# M152B.net
KiCad netlist of a schematic drawn in EAGLE
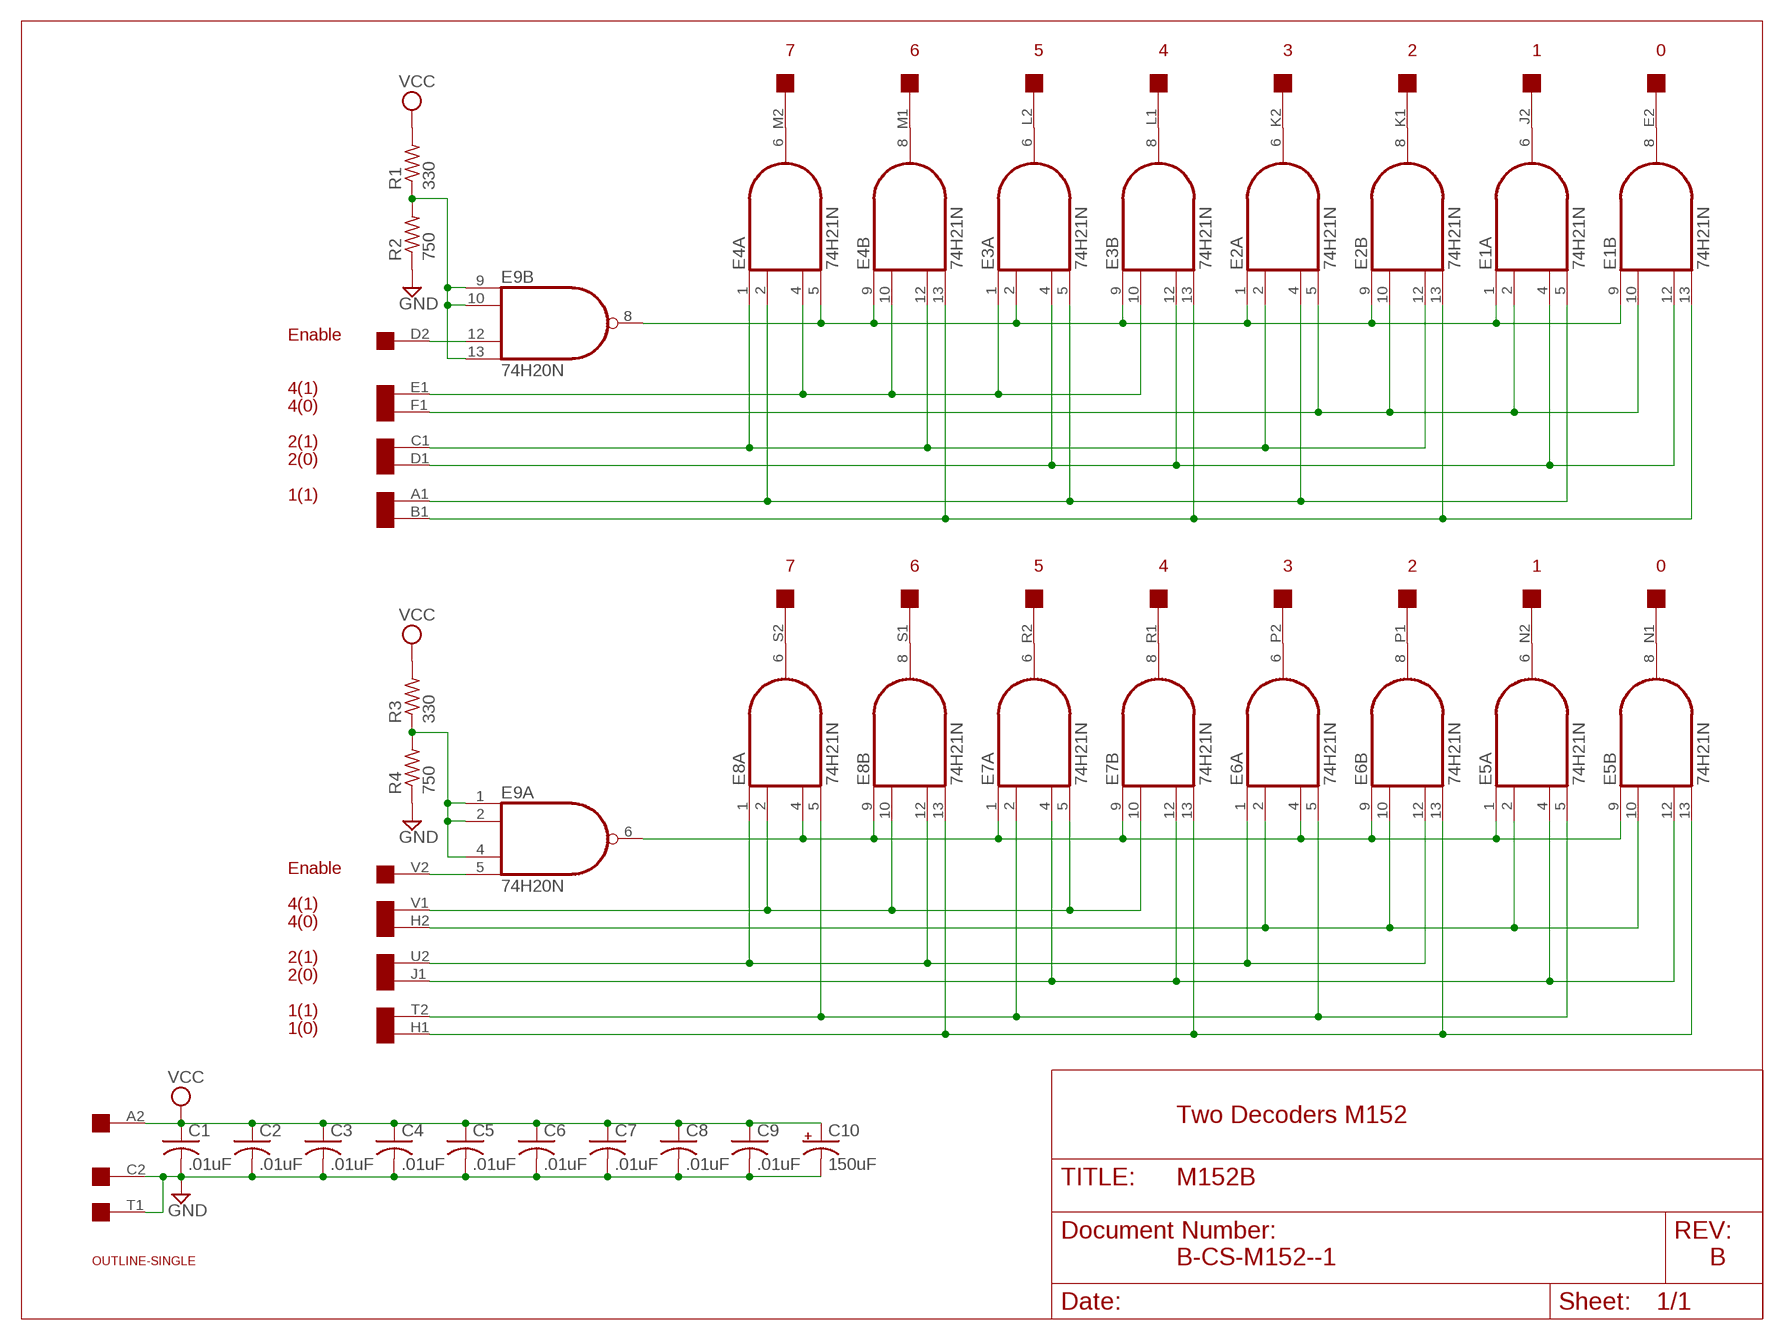
[diagram p0: schematic, sheet 1]

(export (version "E")
  (design (tool "Eeschema 10.0.6"))
  (components
    (comp (ref "C1")
      (value ".01uF")
      (footprint "eagle-import:C050-025X075")
      (libsource (lib "eagle-import") (part "C-US050-025X075"))
    )
    (comp (ref "C2")
      (value ".01uF")
      (footprint "eagle-import:C050-025X075")
      (libsource (lib "eagle-import") (part "C-US050-025X075"))
    )
    (comp (ref "C3")
      (value ".01uF")
      (footprint "eagle-import:C050-025X075")
      (libsource (lib "eagle-import") (part "C-US050-025X075"))
    )
    (comp (ref "C4")
      (value ".01uF")
      (footprint "eagle-import:C050-025X075")
      (libsource (lib "eagle-import") (part "C-US050-025X075"))
    )
    (comp (ref "C5")
      (value ".01uF")
      (footprint "eagle-import:C050-025X075")
      (libsource (lib "eagle-import") (part "C-US050-025X075"))
    )
    (comp (ref "C6")
      (value ".01uF")
      (footprint "eagle-import:C050-025X075")
      (libsource (lib "eagle-import") (part "C-US050-025X075"))
    )
    (comp (ref "C7")
      (value ".01uF")
      (footprint "eagle-import:C050-025X075")
      (libsource (lib "eagle-import") (part "C-US050-025X075"))
    )
    (comp (ref "C8")
      (value ".01uF")
      (footprint "eagle-import:C050-025X075")
      (libsource (lib "eagle-import") (part "C-US050-025X075"))
    )
    (comp (ref "C9")
      (value ".01uF")
      (footprint "eagle-import:C050-025X075")
      (libsource (lib "eagle-import") (part "C-US050-025X075"))
    )
    (comp (ref "C10")
      (value "150uF")
      (footprint "eagle-import:E25-9")
      (libsource (lib "eagle-import") (part "CPOL-USE25-9AXIAL"))
    )
    (comp (ref "E1")
      (value "74H21N")
      (footprint "eagle-import:DIL14")
      (libsource (lib "eagle-import") (part "7421NLS"))
    )
    (comp (ref "E2")
      (value "74H21N")
      (footprint "eagle-import:DIL14")
      (libsource (lib "eagle-import") (part "7421NLS"))
    )
    (comp (ref "E3")
      (value "74H21N")
      (footprint "eagle-import:DIL14")
      (libsource (lib "eagle-import") (part "7421NLS"))
    )
    (comp (ref "E4")
      (value "74H21N")
      (footprint "eagle-import:DIL14")
      (libsource (lib "eagle-import") (part "7421NLS"))
    )
    (comp (ref "E5")
      (value "74H21N")
      (footprint "eagle-import:DIL14")
      (libsource (lib "eagle-import") (part "7421NLS"))
    )
    (comp (ref "E6")
      (value "74H21N")
      (footprint "eagle-import:DIL14")
      (libsource (lib "eagle-import") (part "7421NLS"))
    )
    (comp (ref "E7")
      (value "74H21N")
      (footprint "eagle-import:DIL14")
      (libsource (lib "eagle-import") (part "7421NLS"))
    )
    (comp (ref "E8")
      (value "74H21N")
      (footprint "eagle-import:DIL14")
      (libsource (lib "eagle-import") (part "7421NLS"))
    )
    (comp (ref "E9")
      (value "74H20N")
      (footprint "eagle-import:DIL14")
      (libsource (lib "eagle-import") (part "7420N"))
    )
    (comp (ref "R1")
      (value "330")
      (footprint "eagle-import:0207_10")
      (libsource (lib "eagle-import") (part "R-US_0207/10"))
    )
    (comp (ref "R2")
      (value "750")
      (footprint "eagle-import:0207_10")
      (libsource (lib "eagle-import") (part "R-US_0207/10"))
    )
    (comp (ref "R3")
      (value "330")
      (footprint "eagle-import:0207_10")
      (libsource (lib "eagle-import") (part "R-US_0207/10"))
    )
    (comp (ref "R4")
      (value "750")
      (footprint "eagle-import:0207_10")
      (libsource (lib "eagle-import") (part "R-US_0207/10"))
    )
    (comp (ref "U$1")
      (value "SINGLE")
      (footprint "eagle-import:EDGE-CON2")
      (libsource (lib "eagle-import") (part "SINGLE"))
    )
    (comp (ref "U$2")
      (value "OUTLINE-SINGLE")
      (footprint "eagle-import:SINGLE")
      (libsource (lib "eagle-import") (part "OUTLINE-SINGLE"))
    )
  )
  (nets
    (net (code "1") (name "GND") (class "Default")
      (node (ref "C1") (pin "2") (pinfunction "2_2") (pintype "passive"))
      (node (ref "C10") (pin "-") (pinfunction "-_-") (pintype "passive"))
      (node (ref "C2") (pin "2") (pinfunction "2_2") (pintype "passive"))
      (node (ref "C3") (pin "2") (pinfunction "2_2") (pintype "passive"))
      (node (ref "C4") (pin "2") (pinfunction "2_2") (pintype "passive"))
      (node (ref "C5") (pin "2") (pinfunction "2_2") (pintype "passive"))
      (node (ref "C6") (pin "2") (pinfunction "2_2") (pintype "passive"))
      (node (ref "C7") (pin "2") (pinfunction "2_2") (pintype "passive"))
      (node (ref "C8") (pin "2") (pinfunction "2_2") (pintype "passive"))
      (node (ref "C9") (pin "2") (pinfunction "2_2") (pintype "passive"))
      (node (ref "R2") (pin "1") (pinfunction "1_1") (pintype "passive"))
      (node (ref "R4") (pin "1") (pinfunction "1_1") (pintype "passive"))
      (node (ref "U$1") (pin "C2") (pinfunction "1_C2") (pintype "bidirectional"))
      (node (ref "U$1") (pin "T1") (pinfunction "1_T1") (pintype "bidirectional"))
    )
    (net (code "2") (name "Net-(E1A-I0)") (class "Default")
      (node (ref "E1") (pin "1") (pinfunction "I0_1") (pintype "input"))
      (node (ref "E1") (pin "9") (pinfunction "I0_9") (pintype "input"))
      (node (ref "E2") (pin "1") (pinfunction "I0_1") (pintype "input"))
      (node (ref "E2") (pin "9") (pinfunction "I0_9") (pintype "input"))
      (node (ref "E3") (pin "2") (pinfunction "I1_2") (pintype "input"))
      (node (ref "E3") (pin "9") (pinfunction "I0_9") (pintype "input"))
      (node (ref "E4") (pin "5") (pinfunction "I3_5") (pintype "input"))
      (node (ref "E4") (pin "9") (pinfunction "I0_9") (pintype "input"))
      (node (ref "E9") (pin "8") (pinfunction "O_8") (pintype "output"))
    )
    (net (code "3") (name "Net-(E1A-I1)") (class "Default")
      (node (ref "E1") (pin "10") (pinfunction "I1_10") (pintype "input"))
      (node (ref "E1") (pin "2") (pinfunction "I1_2") (pintype "input"))
      (node (ref "E2") (pin "10") (pinfunction "I1_10") (pintype "input"))
      (node (ref "E2") (pin "5") (pinfunction "I3_5") (pintype "input"))
      (node (ref "U$1") (pin "F1") (pinfunction "1_F1") (pintype "bidirectional"))
    )
    (net (code "4") (name "Net-(E1A-I2)") (class "Default")
      (node (ref "E1") (pin "12") (pinfunction "I2_12") (pintype "input"))
      (node (ref "E1") (pin "4") (pinfunction "I2_4") (pintype "input"))
      (node (ref "E3") (pin "12") (pinfunction "I2_12") (pintype "input"))
      (node (ref "E3") (pin "4") (pinfunction "I2_4") (pintype "input"))
      (node (ref "U$1") (pin "D1") (pinfunction "1_D1") (pintype "bidirectional"))
    )
    (net (code "5") (name "Net-(E1A-I3)") (class "Default")
      (node (ref "E1") (pin "5") (pinfunction "I3_5") (pintype "input"))
      (node (ref "E2") (pin "4") (pinfunction "I2_4") (pintype "input"))
      (node (ref "E3") (pin "5") (pinfunction "I3_5") (pintype "input"))
      (node (ref "E4") (pin "2") (pinfunction "I1_2") (pintype "input"))
      (node (ref "U$1") (pin "A1") (pinfunction "1_A1") (pintype "bidirectional"))
    )
    (net (code "6") (name "Net-(E1A-O)") (class "Default")
      (node (ref "E1") (pin "6") (pinfunction "O_6") (pintype "output"))
      (node (ref "U$1") (pin "J2") (pinfunction "1_J2") (pintype "bidirectional"))
    )
    (net (code "7") (name "Net-(E1B-I3)") (class "Default")
      (node (ref "E1") (pin "13") (pinfunction "I3_13") (pintype "input"))
      (node (ref "E2") (pin "13") (pinfunction "I3_13") (pintype "input"))
      (node (ref "E3") (pin "13") (pinfunction "I3_13") (pintype "input"))
      (node (ref "E4") (pin "13") (pinfunction "I3_13") (pintype "input"))
      (node (ref "U$1") (pin "B1") (pinfunction "1_B1") (pintype "bidirectional"))
    )
    (net (code "8") (name "Net-(E1B-O)") (class "Default")
      (node (ref "E1") (pin "8") (pinfunction "O_8") (pintype "output"))
      (node (ref "U$1") (pin "E2") (pinfunction "1_E2") (pintype "bidirectional"))
    )
    (net (code "9") (name "Net-(E2A-I1)") (class "Default")
      (node (ref "E2") (pin "12") (pinfunction "I2_12") (pintype "input"))
      (node (ref "E2") (pin "2") (pinfunction "I1_2") (pintype "input"))
      (node (ref "E4") (pin "1") (pinfunction "I0_1") (pintype "input"))
      (node (ref "E4") (pin "12") (pinfunction "I2_12") (pintype "input"))
      (node (ref "U$1") (pin "C1") (pinfunction "1_C1") (pintype "bidirectional"))
    )
    (net (code "10") (name "Net-(E2A-O)") (class "Default")
      (node (ref "E2") (pin "6") (pinfunction "O_6") (pintype "output"))
      (node (ref "U$1") (pin "K2") (pinfunction "1_K2") (pintype "bidirectional"))
    )
    (net (code "11") (name "Net-(E2B-O)") (class "Default")
      (node (ref "E2") (pin "8") (pinfunction "O_8") (pintype "output"))
      (node (ref "U$1") (pin "K1") (pinfunction "1_K1") (pintype "bidirectional"))
    )
    (net (code "12") (name "Net-(E3A-I0)") (class "Default")
      (node (ref "E3") (pin "1") (pinfunction "I0_1") (pintype "input"))
      (node (ref "E3") (pin "10") (pinfunction "I1_10") (pintype "input"))
      (node (ref "E4") (pin "10") (pinfunction "I1_10") (pintype "input"))
      (node (ref "E4") (pin "4") (pinfunction "I2_4") (pintype "input"))
      (node (ref "U$1") (pin "E1") (pinfunction "1_E1") (pintype "bidirectional"))
    )
    (net (code "13") (name "Net-(E3A-O)") (class "Default")
      (node (ref "E3") (pin "6") (pinfunction "O_6") (pintype "output"))
      (node (ref "U$1") (pin "L2") (pinfunction "1_L2") (pintype "bidirectional"))
    )
    (net (code "14") (name "Net-(E3B-O)") (class "Default")
      (node (ref "E3") (pin "8") (pinfunction "O_8") (pintype "output"))
      (node (ref "U$1") (pin "L1") (pinfunction "1_L1") (pintype "bidirectional"))
    )
    (net (code "15") (name "Net-(E4A-O)") (class "Default")
      (node (ref "E4") (pin "6") (pinfunction "O_6") (pintype "output"))
      (node (ref "U$1") (pin "M2") (pinfunction "1_M2") (pintype "bidirectional"))
    )
    (net (code "16") (name "Net-(E4B-O)") (class "Default")
      (node (ref "E4") (pin "8") (pinfunction "O_8") (pintype "output"))
      (node (ref "U$1") (pin "M1") (pinfunction "1_M1") (pintype "bidirectional"))
    )
    (net (code "17") (name "Net-(E5A-I0)") (class "Default")
      (node (ref "E5") (pin "1") (pinfunction "I0_1") (pintype "input"))
      (node (ref "E5") (pin "9") (pinfunction "I0_9") (pintype "input"))
      (node (ref "E6") (pin "4") (pinfunction "I2_4") (pintype "input"))
      (node (ref "E6") (pin "9") (pinfunction "I0_9") (pintype "input"))
      (node (ref "E7") (pin "1") (pinfunction "I0_1") (pintype "input"))
      (node (ref "E7") (pin "9") (pinfunction "I0_9") (pintype "input"))
      (node (ref "E8") (pin "4") (pinfunction "I2_4") (pintype "input"))
      (node (ref "E8") (pin "9") (pinfunction "I0_9") (pintype "input"))
      (node (ref "E9") (pin "6") (pinfunction "O_6") (pintype "output"))
    )
    (net (code "18") (name "Net-(E5A-I1)") (class "Default")
      (node (ref "E5") (pin "10") (pinfunction "I1_10") (pintype "input"))
      (node (ref "E5") (pin "2") (pinfunction "I1_2") (pintype "input"))
      (node (ref "E6") (pin "10") (pinfunction "I1_10") (pintype "input"))
      (node (ref "E6") (pin "2") (pinfunction "I1_2") (pintype "input"))
      (node (ref "U$1") (pin "H2") (pinfunction "1_H2") (pintype "bidirectional"))
    )
    (net (code "19") (name "Net-(E5A-I2)") (class "Default")
      (node (ref "E5") (pin "12") (pinfunction "I2_12") (pintype "input"))
      (node (ref "E5") (pin "4") (pinfunction "I2_4") (pintype "input"))
      (node (ref "E7") (pin "12") (pinfunction "I2_12") (pintype "input"))
      (node (ref "E7") (pin "4") (pinfunction "I2_4") (pintype "input"))
      (node (ref "U$1") (pin "J1") (pinfunction "1_J1") (pintype "bidirectional"))
    )
    (net (code "20") (name "Net-(E5A-I3)") (class "Default")
      (node (ref "E5") (pin "5") (pinfunction "I3_5") (pintype "input"))
      (node (ref "E6") (pin "5") (pinfunction "I3_5") (pintype "input"))
      (node (ref "E7") (pin "2") (pinfunction "I1_2") (pintype "input"))
      (node (ref "E8") (pin "5") (pinfunction "I3_5") (pintype "input"))
      (node (ref "U$1") (pin "T2") (pinfunction "1_T2") (pintype "bidirectional"))
    )
    (net (code "21") (name "Net-(E5A-O)") (class "Default")
      (node (ref "E5") (pin "6") (pinfunction "O_6") (pintype "output"))
      (node (ref "U$1") (pin "N2") (pinfunction "1_N2") (pintype "bidirectional"))
    )
    (net (code "22") (name "Net-(E5B-I3)") (class "Default")
      (node (ref "E5") (pin "13") (pinfunction "I3_13") (pintype "input"))
      (node (ref "E6") (pin "13") (pinfunction "I3_13") (pintype "input"))
      (node (ref "E7") (pin "13") (pinfunction "I3_13") (pintype "input"))
      (node (ref "E8") (pin "13") (pinfunction "I3_13") (pintype "input"))
      (node (ref "U$1") (pin "H1") (pinfunction "1_H1") (pintype "bidirectional"))
    )
    (net (code "23") (name "Net-(E5B-O)") (class "Default")
      (node (ref "E5") (pin "8") (pinfunction "O_8") (pintype "output"))
      (node (ref "U$1") (pin "N1") (pinfunction "1_N1") (pintype "bidirectional"))
    )
    (net (code "24") (name "Net-(E6A-I0)") (class "Default")
      (node (ref "E6") (pin "1") (pinfunction "I0_1") (pintype "input"))
      (node (ref "E6") (pin "12") (pinfunction "I2_12") (pintype "input"))
      (node (ref "E8") (pin "1") (pinfunction "I0_1") (pintype "input"))
      (node (ref "E8") (pin "12") (pinfunction "I2_12") (pintype "input"))
      (node (ref "U$1") (pin "U2") (pinfunction "1_U2") (pintype "bidirectional"))
    )
    (net (code "25") (name "Net-(E6A-O)") (class "Default")
      (node (ref "E6") (pin "6") (pinfunction "O_6") (pintype "output"))
      (node (ref "U$1") (pin "P2") (pinfunction "1_P2") (pintype "bidirectional"))
    )
    (net (code "26") (name "Net-(E6B-O)") (class "Default")
      (node (ref "E6") (pin "8") (pinfunction "O_8") (pintype "output"))
      (node (ref "U$1") (pin "P1") (pinfunction "1_P1") (pintype "bidirectional"))
    )
    (net (code "27") (name "Net-(E7A-I3)") (class "Default")
      (node (ref "E7") (pin "10") (pinfunction "I1_10") (pintype "input"))
      (node (ref "E7") (pin "5") (pinfunction "I3_5") (pintype "input"))
      (node (ref "E8") (pin "10") (pinfunction "I1_10") (pintype "input"))
      (node (ref "E8") (pin "2") (pinfunction "I1_2") (pintype "input"))
      (node (ref "U$1") (pin "V1") (pinfunction "1_V1") (pintype "bidirectional"))
    )
    (net (code "28") (name "Net-(E7A-O)") (class "Default")
      (node (ref "E7") (pin "6") (pinfunction "O_6") (pintype "output"))
      (node (ref "U$1") (pin "R2") (pinfunction "1_R2") (pintype "bidirectional"))
    )
    (net (code "29") (name "Net-(E7B-O)") (class "Default")
      (node (ref "E7") (pin "8") (pinfunction "O_8") (pintype "output"))
      (node (ref "U$1") (pin "R1") (pinfunction "1_R1") (pintype "bidirectional"))
    )
    (net (code "30") (name "Net-(E8A-O)") (class "Default")
      (node (ref "E8") (pin "6") (pinfunction "O_6") (pintype "output"))
      (node (ref "U$1") (pin "S2") (pinfunction "1_S2") (pintype "bidirectional"))
    )
    (net (code "31") (name "Net-(E8B-O)") (class "Default")
      (node (ref "E8") (pin "8") (pinfunction "O_8") (pintype "output"))
      (node (ref "U$1") (pin "S1") (pinfunction "1_S1") (pintype "bidirectional"))
    )
    (net (code "32") (name "Net-(E9C-I0)") (class "Default")
      (node (ref "E9") (pin "1") (pinfunction "I0_1") (pintype "input"))
      (node (ref "E9") (pin "2") (pinfunction "I1_2") (pintype "input"))
      (node (ref "E9") (pin "4") (pinfunction "I2_4") (pintype "input"))
      (node (ref "R3") (pin "1") (pinfunction "1_1") (pintype "passive"))
      (node (ref "R4") (pin "2") (pinfunction "2_2") (pintype "passive"))
    )
    (net (code "33") (name "Net-(E9C-I3)") (class "Default")
      (node (ref "E9") (pin "5") (pinfunction "I3_5") (pintype "input"))
      (node (ref "U$1") (pin "V2") (pinfunction "1_V2") (pintype "bidirectional"))
    )
    (net (code "34") (name "Net-(E9D-I0)") (class "Default")
      (node (ref "E9") (pin "10") (pinfunction "I1_10") (pintype "input"))
      (node (ref "E9") (pin "13") (pinfunction "I3_13") (pintype "input"))
      (node (ref "E9") (pin "9") (pinfunction "I0_9") (pintype "input"))
      (node (ref "R1") (pin "1") (pinfunction "1_1") (pintype "passive"))
      (node (ref "R2") (pin "2") (pinfunction "2_2") (pintype "passive"))
    )
    (net (code "35") (name "Net-(E9D-I2)") (class "Default")
      (node (ref "E9") (pin "12") (pinfunction "I2_12") (pintype "input"))
      (node (ref "U$1") (pin "D2") (pinfunction "1_D2") (pintype "bidirectional"))
    )
    (net (code "36") (name "VCC") (class "Default")
      (node (ref "C1") (pin "1") (pinfunction "1_1") (pintype "passive"))
      (node (ref "C10") (pin "+") (pinfunction "+_+") (pintype "passive"))
      (node (ref "C2") (pin "1") (pinfunction "1_1") (pintype "passive"))
      (node (ref "C3") (pin "1") (pinfunction "1_1") (pintype "passive"))
      (node (ref "C4") (pin "1") (pinfunction "1_1") (pintype "passive"))
      (node (ref "C5") (pin "1") (pinfunction "1_1") (pintype "passive"))
      (node (ref "C6") (pin "1") (pinfunction "1_1") (pintype "passive"))
      (node (ref "C7") (pin "1") (pinfunction "1_1") (pintype "passive"))
      (node (ref "C8") (pin "1") (pinfunction "1_1") (pintype "passive"))
      (node (ref "C9") (pin "1") (pinfunction "1_1") (pintype "passive"))
      (node (ref "R1") (pin "2") (pinfunction "2_2") (pintype "passive"))
      (node (ref "R3") (pin "2") (pinfunction "2_2") (pintype "passive"))
      (node (ref "U$1") (pin "A2") (pinfunction "1_A2") (pintype "bidirectional"))
    )
  )
)
